# Reference.net
KiCad netlist of a schematic drawn in Altium Designer
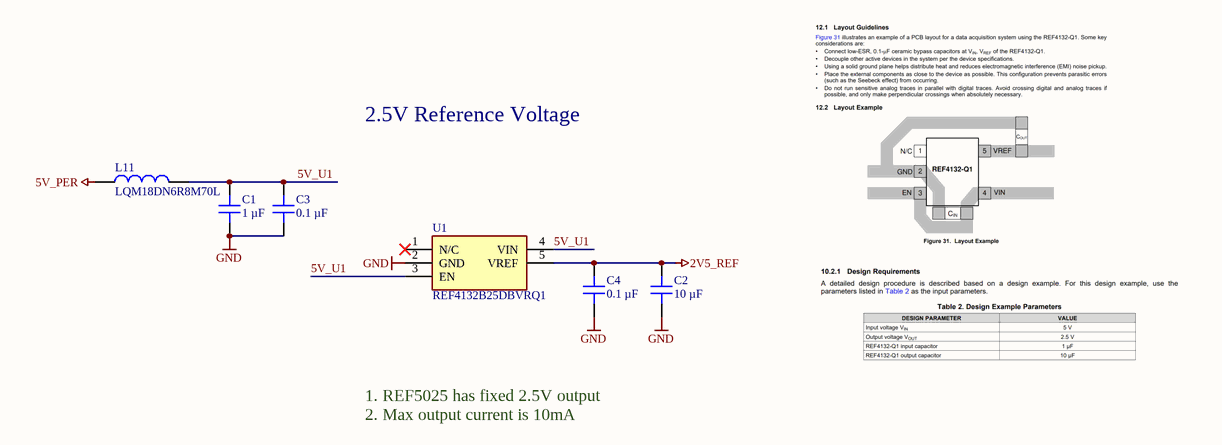
[diagram p0: Reference.SchDoc]

(export (version "E")
  (design (tool "Eeschema 10.0.6"))
  (components
    (comp (ref "C1")
      (value "1 µF")
      (footprint "C_0603")
      (description "Capacitor 0603, 25 VDC, 1 µF, X7R")
      (fields
        (field (name "MANUFACTURER PART NUMBER") "C0603C105K3RAC7411")
        (field (name "MANUFACTURER") "KEMET")
        (field (name "CREATED FROM") "MGremer")
      )
      (libsource (lib "user") (part "Capacitor"))
    )
    (comp (ref "C2")
      (value "10 µF")
      (footprint "C_1210_N")
      (description "Capacitor 1210, 100 VDC, 10µF, X7S")
      (fields
        (field (name "MANUFACTURER PART NUMBER") "GRM32EC72A106KE05L")
        (field (name "MANUFACTURER") "Murata Electronics")
        (field (name "CREATED FROM") "DHufnagel")
      )
      (libsource (lib "user") (part "Capacitor"))
    )
    (comp (ref "C3")
      (value "0.1 µF")
      (footprint "C_0603")
      (description "Capacitor 0603, 100 VDC, 0.1 uF, X7S")
      (fields
        (field (name "MANUFACTURER PART NUMBER") "C1608X7S2A104K080AB")
        (field (name "MANUFACTURER") "TDK")
        (field (name "CREATED FROM") "DHufnagel")
      )
      (libsource (lib "user") (part "Capacitor"))
    )
    (comp (ref "C4")
      (value "0.1 µF")
      (footprint "C_0603")
      (description "Capacitor 0603, 100 VDC, 0.1 uF, X7S")
      (fields
        (field (name "MANUFACTURER PART NUMBER") "C1608X7S2A104K080AB")
        (field (name "MANUFACTURER") "TDK")
        (field (name "CREATED FROM") "DHufnagel")
      )
      (libsource (lib "user") (part "Capacitor"))
    )
    (comp (ref "L11")
      (value "LQM18DN6R8M70L")
      (footprint "INDC1608X95N")
      (description "6.8µH, 120mA, 0603, 740mOhm, 20%")
      (fields
        (field (name "MF") "EPCOS / TDK")
        (field (name "MPN") "B82464G4154M")
        (field (name "CREATED FROM") "DHufnagel")
      )
      (libsource (lib "user") (part "B82464G4154M"))
    )
    (comp (ref "U1")
      (value "REF4132B25DBVRQ1")
      (footprint "SOT95P280X145-5N")
      (description "Voltage Reference, 2.5V, ±0.05%, ±10mA")
      (fields (field (name "MANUFACTURER") "Texas Instruments") (field (name "CREATED FROM") "DHufnagel"))
      (libsource (lib "user") (part "REF4132B25DBVRQ1"))
    )
  )
  (nets
    (net (code "1") (name "/5V_U1") (class "Default")
      (node (ref "C1") (pin "2") (pinfunction "2_2") (pintype "passive"))
      (node (ref "C3") (pin "2") (pinfunction "2_2") (pintype "passive"))
      (node (ref "L11") (pin "2") (pinfunction "2_2") (pintype "passive"))
      (node (ref "U1") (pin "3") (pinfunction "EN_3") (pintype "passive"))
      (node (ref "U1") (pin "4") (pinfunction "VIN_4") (pintype "passive"))
    )
    (net (code "2") (name "2V5_REF") (class "Default")
      (node (ref "C2") (pin "2") (pinfunction "2_2") (pintype "passive"))
      (node (ref "C4") (pin "2") (pinfunction "2_2") (pintype "passive"))
      (node (ref "U1") (pin "5") (pinfunction "VREF_5") (pintype "passive"))
    )
    (net (code "3") (name "5V_PER") (class "Default")
      (node (ref "L11") (pin "1") (pinfunction "1_1") (pintype "passive"))
    )
    (net (code "4") (name "GND") (class "Default")
      (node (ref "C1") (pin "1") (pinfunction "1_1") (pintype "passive"))
      (node (ref "C2") (pin "1") (pinfunction "1_1") (pintype "passive"))
      (node (ref "C3") (pin "1") (pinfunction "1_1") (pintype "passive"))
      (node (ref "C4") (pin "1") (pinfunction "1_1") (pintype "passive"))
      (node (ref "U1") (pin "2") (pinfunction "GND_2") (pintype "passive"))
    )
    (net (code "5") (name "unconnected-(U1-N{slash}C-Pad1)") (class "Default")
      (node (ref "U1") (pin "1") (pinfunction "N/C_1") (pintype "passive+no_connect"))
    )
  )
)
